# OverCurrent_Indicators.net
KiCad netlist of a schematic drawn in Altium Designer
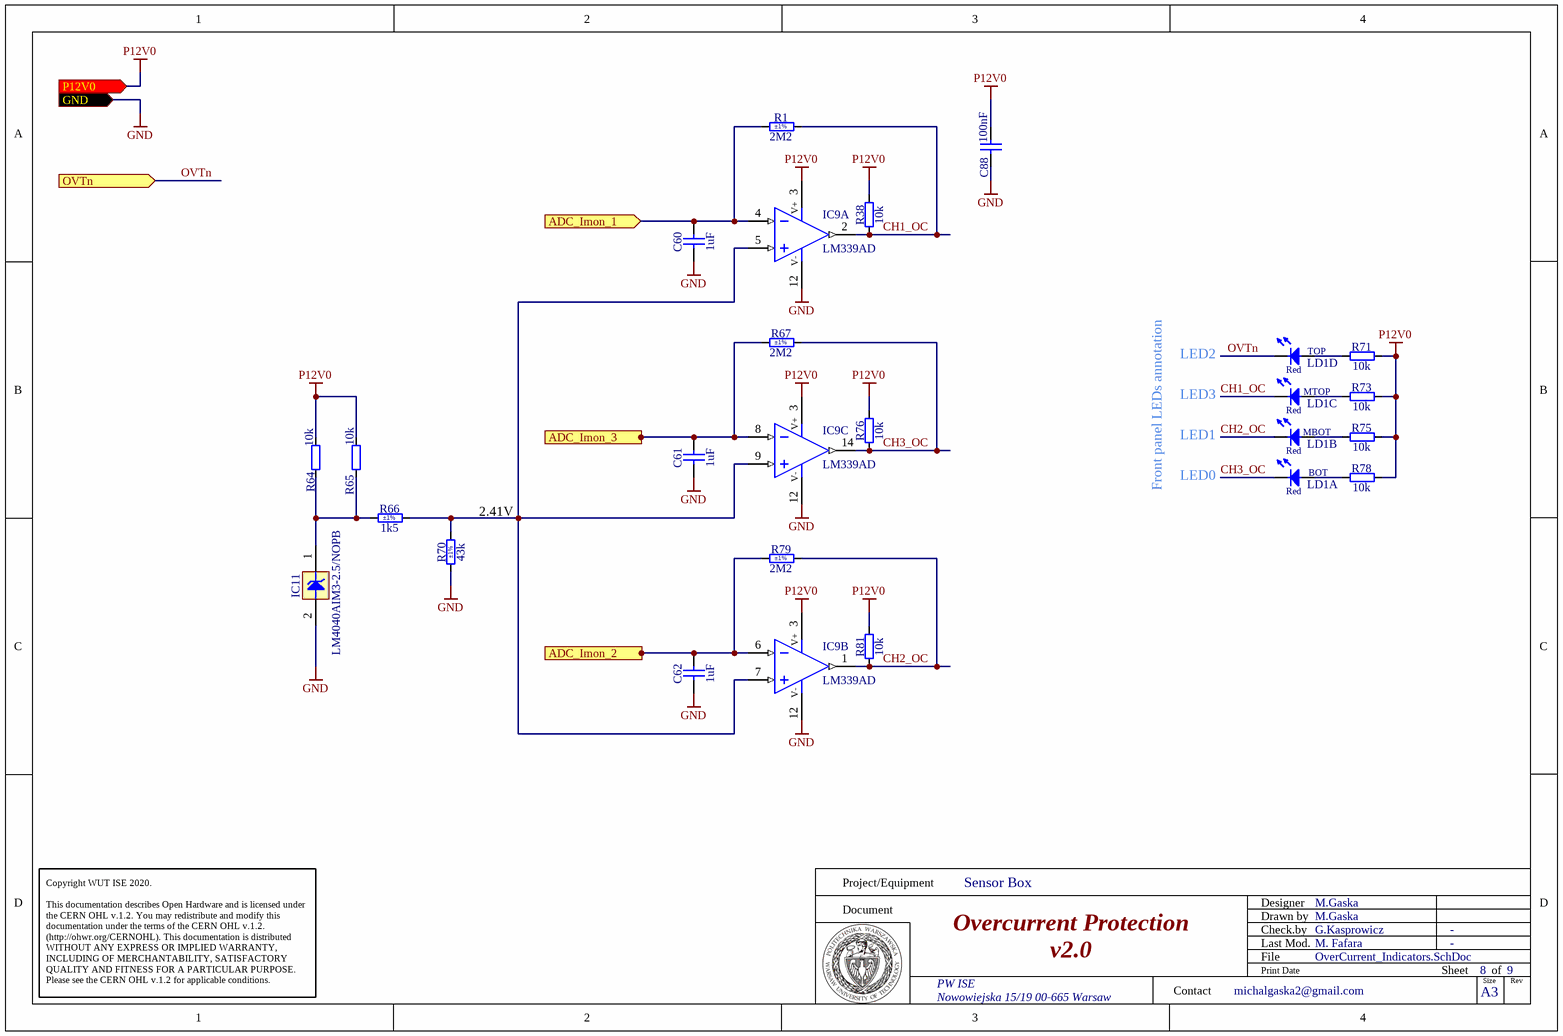
[diagram p0: OverCurrent_Indicators.SchDoc]

(export (version "E")
  (design (tool "Eeschema 10.0.6"))
  (components
    (comp (ref "C60")
      (value "1uF")
      (footprint "CAPC1608X87N")
      (description "Non-polarised capacitor")
      (fields
        (field (name "PART NUMBER") "CC0603_1UF_25V_10%_X7R")
        (field (name "VOLTAGE") "25V")
        (field (name "AUTHOR") "CERN DEM JLC")
      )
      (libsource (lib "Capacitors") (part "Capacitor - non polarized"))
    )
    (comp (ref "C61")
      (value "1uF")
      (footprint "CAPC1608X87N")
      (description "Non-polarised capacitor")
      (fields
        (field (name "PART NUMBER") "CC0603_1UF_25V_10%_X7R")
        (field (name "VOLTAGE") "25V")
        (field (name "AUTHOR") "CERN DEM JLC")
      )
      (libsource (lib "Capacitors") (part "Capacitor - non polarized"))
    )
    (comp (ref "C62")
      (value "1uF")
      (footprint "CAPC1608X87N")
      (description "Non-polarised capacitor")
      (fields
        (field (name "PART NUMBER") "CC0603_1UF_25V_10%_X7R")
        (field (name "VOLTAGE") "25V")
        (field (name "AUTHOR") "CERN DEM JLC")
      )
      (libsource (lib "Capacitors") (part "Capacitor - non polarized"))
    )
    (comp (ref "C88")
      (value "100nF")
      (footprint "CAPC1608X87N")
      (description "Non-polarised capacitor")
      (fields
        (field (name "PART NUMBER") "CC0603_100NF_50V_10%_X7R")
        (field (name "VOLTAGE") "50V")
        (field (name "AUTHOR") "CERN DEM JLC")
      )
      (libsource (lib "Capacitors") (part "Capacitor - non polarized"))
    )
    (comp (ref "IC9")
      (value "LM339AD")
      (footprint "SOIC127P600X175-14N")
      (description "Quad Operational Amplifier")
      (fields (field (name "MANUFACTURER") "TEXAS INSTRUMENTS") (field (name "AUTHOR") "CERN DEM JLC"))
      (libsource (lib "ICs And Semiconductors") (part "Operational Amplifier x4 Type2"))
    )
    (comp (ref "IC11")
      (value "LM4040AIM3-2.5/NOPB")
      (footprint "SOT95P251X112-3N")
      (description "Precision Micropower Shunt Voltage Reference")
      (fields
        (field (name "MANUFACTURER") "TEXAS INSTRUMENTS")
        (field (name "MANUFACTURER PART NUMBER") "LM4040AIM3-2.5")
        (field (name "AUTHOR") "CERN DEM JLC")
      )
      (libsource (lib "ICs And Semiconductors") (part "LM4040AIM3"))
    )
    (comp (ref "LD1")
      (value "~")
      (footprint "LED_BIVAR_H485CHDL")
      (description "LED x4 Red 1C2A-BOT_3C4A_5C6A_7C8A-TOP")
      (fields
        (field (name "PART NUMBER") "LED_BIVAR_H485CHDL")
        (field (name "MANUFACTURER") "BIVAR")
        (field (name "AUTHOR") "CERN DEM JLC")
      )
      (libsource (lib "ICs And Semiconductors") (part "LED x4 Red 1C2A-BOT_3C4A_5C6A_7C8A-TOP"))
    )
    (comp (ref "R1")
      (value "2M2")
      (footprint "RESC1608X55N")
      (description "Resistor - 1%")
      (fields
        (field (name "TOLERANCE") "±1%")
        (field (name "PART NUMBER") "R0603_2M2_1%_0.1W_100PPM")
        (field (name "POWER") "0.1W")
        (field (name "AUTHOR") "CERN DEM JLC")
      )
      (libsource (lib "Resistors") (part "Resistor - 1%"))
    )
    (comp (ref "R38")
      (value "10k")
      (footprint "RESC1608X55N")
      (description "Resistor - 1%")
      (fields
        (field (name "PART NUMBER") "R0603_10K_1%_0.1W_100PPM")
        (field (name "POWER") "0.1W")
        (field (name "AUTHOR") "CERN DEM JLC")
      )
      (libsource (lib "Resistors") (part "Resistor - 1%"))
    )
    (comp (ref "R64")
      (value "10k")
      (footprint "RESC1608X55N")
      (description "Resistor - 1%")
      (fields
        (field (name "PART NUMBER") "R0603_10K_1%_0.1W_100PPM")
        (field (name "POWER") "0.1W")
        (field (name "AUTHOR") "CERN DEM JLC")
      )
      (libsource (lib "Resistors") (part "Resistor - 1%"))
    )
    (comp (ref "R65")
      (value "10k")
      (footprint "RESC1608X55N")
      (description "Resistor - 1%")
      (fields
        (field (name "PART NUMBER") "R0603_10K_1%_0.1W_100PPM")
        (field (name "POWER") "0.1W")
        (field (name "AUTHOR") "CERN DEM JLC")
      )
      (libsource (lib "Resistors") (part "Resistor - 1%"))
    )
    (comp (ref "R66")
      (value "1k5")
      (footprint "RESC1608X55N")
      (description "Resistor - 1%")
      (fields
        (field (name "TOLERANCE") "±1%")
        (field (name "PART NUMBER") "R0603_1K5_1%_0.1W_100PPM")
        (field (name "POWER") "0.1W")
        (field (name "AUTHOR") "CERN DEM JLC")
      )
      (libsource (lib "Resistors") (part "Resistor - 1%"))
    )
    (comp (ref "R67")
      (value "2M2")
      (footprint "RESC1608X55N")
      (description "Resistor - 1%")
      (fields
        (field (name "TOLERANCE") "±1%")
        (field (name "PART NUMBER") "R0603_2M2_1%_0.1W_100PPM")
        (field (name "POWER") "0.1W")
        (field (name "AUTHOR") "CERN DEM JLC")
      )
      (libsource (lib "Resistors") (part "Resistor - 1%"))
    )
    (comp (ref "R70")
      (value "43k")
      (footprint "RESC1608X55N")
      (description "Resistor - 1%")
      (fields
        (field (name "TOLERANCE") "±1%")
        (field (name "PART NUMBER") "R0603_43K_1%_0.1W_100PPM")
        (field (name "POWER") "0.1W")
        (field (name "AUTHOR") "CERN DEM JLC")
      )
      (libsource (lib "Resistors") (part "Resistor - 1%"))
    )
    (comp (ref "R71")
      (value "10k")
      (footprint "RESC1608X55N")
      (description "Resistor - 1%")
      (fields
        (field (name "PART NUMBER") "R0603_10K_1%_0.1W_100PPM")
        (field (name "POWER") "0.1W")
        (field (name "AUTHOR") "CERN DEM JLC")
      )
      (libsource (lib "Resistors") (part "Resistor - 1%"))
    )
    (comp (ref "R73")
      (value "10k")
      (footprint "RESC1608X55N")
      (description "Resistor - 1%")
      (fields
        (field (name "PART NUMBER") "R0603_10K_1%_0.1W_100PPM")
        (field (name "POWER") "0.1W")
        (field (name "AUTHOR") "CERN DEM JLC")
      )
      (libsource (lib "Resistors") (part "Resistor - 1%"))
    )
    (comp (ref "R75")
      (value "10k")
      (footprint "RESC1608X55N")
      (description "Resistor - 1%")
      (fields
        (field (name "PART NUMBER") "R0603_10K_1%_0.1W_100PPM")
        (field (name "POWER") "0.1W")
        (field (name "AUTHOR") "CERN DEM JLC")
      )
      (libsource (lib "Resistors") (part "Resistor - 1%"))
    )
    (comp (ref "R76")
      (value "10k")
      (footprint "RESC1608X55N")
      (description "Resistor - 1%")
      (fields
        (field (name "PART NUMBER") "R0603_10K_1%_0.1W_100PPM")
        (field (name "POWER") "0.1W")
        (field (name "AUTHOR") "CERN DEM JLC")
      )
      (libsource (lib "Resistors") (part "Resistor - 1%"))
    )
    (comp (ref "R78")
      (value "10k")
      (footprint "RESC1608X55N")
      (description "Resistor - 1%")
      (fields
        (field (name "PART NUMBER") "R0603_10K_1%_0.1W_100PPM")
        (field (name "POWER") "0.1W")
        (field (name "AUTHOR") "CERN DEM JLC")
      )
      (libsource (lib "Resistors") (part "Resistor - 1%"))
    )
    (comp (ref "R79")
      (value "2M2")
      (footprint "RESC1608X55N")
      (description "Resistor - 1%")
      (fields
        (field (name "TOLERANCE") "±1%")
        (field (name "PART NUMBER") "R0603_2M2_1%_0.1W_100PPM")
        (field (name "POWER") "0.1W")
        (field (name "AUTHOR") "CERN DEM JLC")
      )
      (libsource (lib "Resistors") (part "Resistor - 1%"))
    )
    (comp (ref "R81")
      (value "10k")
      (footprint "RESC1608X55N")
      (description "Resistor - 1%")
      (fields
        (field (name "PART NUMBER") "R0603_10K_1%_0.1W_100PPM")
        (field (name "POWER") "0.1W")
        (field (name "AUTHOR") "CERN DEM JLC")
      )
      (libsource (lib "Resistors") (part "Resistor - 1%"))
    )
  )
  (nets
    (net (code "1") (name "/ADC_Imon_1") (class "Default")
      (node (ref "C60") (pin "2") (pinfunction "2_2") (pintype "passive"))
      (node (ref "IC9") (pin "4") (pinfunction "IN-_4") (pintype "input"))
      (node (ref "R1") (pin "1") (pinfunction "1_1") (pintype "passive"))
    )
    (net (code "2") (name "/ADC_Imon_2") (class "Default")
      (node (ref "C62") (pin "2") (pinfunction "2_2") (pintype "passive"))
      (node (ref "IC9") (pin "6") (pinfunction "IN-_6") (pintype "input"))
      (node (ref "R79") (pin "1") (pinfunction "1_1") (pintype "passive"))
    )
    (net (code "3") (name "/ADC_Imon_3") (class "Default")
      (node (ref "C61") (pin "2") (pinfunction "2_2") (pintype "passive"))
      (node (ref "IC9") (pin "8") (pinfunction "IN-_8") (pintype "input"))
      (node (ref "R67") (pin "1") (pinfunction "1_1") (pintype "passive"))
    )
    (net (code "4") (name "/CH1_OC") (class "Default")
      (node (ref "IC9") (pin "2") (pinfunction "OUT_2") (pintype "output"))
      (node (ref "LD1") (pin "5") (pinfunction "C_5") (pintype "passive"))
      (node (ref "R1") (pin "2") (pinfunction "2_2") (pintype "passive"))
      (node (ref "R38") (pin "1") (pinfunction "1_1") (pintype "passive"))
    )
    (net (code "5") (name "/CH2_OC") (class "Default")
      (node (ref "IC9") (pin "1") (pinfunction "OUT_1") (pintype "output"))
      (node (ref "LD1") (pin "3") (pinfunction "C_3") (pintype "passive"))
      (node (ref "R79") (pin "2") (pinfunction "2_2") (pintype "passive"))
      (node (ref "R81") (pin "1") (pinfunction "1_1") (pintype "passive"))
    )
    (net (code "6") (name "/CH3_OC") (class "Default")
      (node (ref "IC9") (pin "14") (pinfunction "OUT_14") (pintype "output"))
      (node (ref "LD1") (pin "1") (pinfunction "C_1") (pintype "passive"))
      (node (ref "R67") (pin "2") (pinfunction "2_2") (pintype "passive"))
      (node (ref "R76") (pin "1") (pinfunction "1_1") (pintype "passive"))
    )
    (net (code "7") (name "/OVTn") (class "Default")
      (node (ref "LD1") (pin "7") (pinfunction "C_7") (pintype "passive"))
    )
    (net (code "8") (name "GND") (class "Default")
      (node (ref "C60") (pin "1") (pinfunction "1_1") (pintype "passive"))
      (node (ref "C61") (pin "1") (pinfunction "1_1") (pintype "passive"))
      (node (ref "C62") (pin "1") (pinfunction "1_1") (pintype "passive"))
      (node (ref "C88") (pin "1") (pinfunction "1_1") (pintype "passive"))
      (node (ref "IC11") (pin "2") (pinfunction "A_2") (pintype "passive"))
      (node (ref "IC9") (pin "12") (pinfunction "V-_12") (pintype "power_in"))
      (node (ref "R70") (pin "1") (pinfunction "1_1") (pintype "passive"))
    )
    (net (code "9") (name "Net-(IC9A-IN+)") (class "Default")
      (node (ref "IC9") (pin "5") (pinfunction "IN+_5") (pintype "input"))
      (node (ref "IC9") (pin "7") (pinfunction "IN+_7") (pintype "input"))
      (node (ref "IC9") (pin "9") (pinfunction "IN+_9") (pintype "input"))
      (node (ref "R66") (pin "2") (pinfunction "2_2") (pintype "passive"))
      (node (ref "R70") (pin "2") (pinfunction "2_2") (pintype "passive"))
    )
    (net (code "10") (name "Net-(IC11-C)") (class "Default")
      (node (ref "IC11") (pin "1") (pinfunction "C_1") (pintype "passive"))
      (node (ref "R64") (pin "1") (pinfunction "1_1") (pintype "passive"))
      (node (ref "R65") (pin "1") (pinfunction "1_1") (pintype "passive"))
      (node (ref "R66") (pin "1") (pinfunction "1_1") (pintype "passive"))
    )
    (net (code "11") (name "Net-(LD1A-A)") (class "Default")
      (node (ref "LD1") (pin "2") (pinfunction "A_2") (pintype "passive"))
      (node (ref "R78") (pin "2") (pinfunction "2_2") (pintype "passive"))
    )
    (net (code "12") (name "Net-(LD1B-A)") (class "Default")
      (node (ref "LD1") (pin "4") (pinfunction "A_4") (pintype "passive"))
      (node (ref "R75") (pin "2") (pinfunction "2_2") (pintype "passive"))
    )
    (net (code "13") (name "Net-(LD1C-A)") (class "Default")
      (node (ref "LD1") (pin "6") (pinfunction "A_6") (pintype "passive"))
      (node (ref "R73") (pin "2") (pinfunction "2_2") (pintype "passive"))
    )
    (net (code "14") (name "Net-(LD1D-A)") (class "Default")
      (node (ref "LD1") (pin "8") (pinfunction "A_8") (pintype "passive"))
      (node (ref "R71") (pin "2") (pinfunction "2_2") (pintype "passive"))
    )
    (net (code "15") (name "P12V0") (class "Default")
      (node (ref "C88") (pin "2") (pinfunction "2_2") (pintype "passive"))
      (node (ref "IC9") (pin "3") (pinfunction "V+_3") (pintype "power_in"))
      (node (ref "R38") (pin "2") (pinfunction "2_2") (pintype "passive"))
      (node (ref "R64") (pin "2") (pinfunction "2_2") (pintype "passive"))
      (node (ref "R65") (pin "2") (pinfunction "2_2") (pintype "passive"))
      (node (ref "R71") (pin "1") (pinfunction "1_1") (pintype "passive"))
      (node (ref "R73") (pin "1") (pinfunction "1_1") (pintype "passive"))
      (node (ref "R75") (pin "1") (pinfunction "1_1") (pintype "passive"))
      (node (ref "R76") (pin "2") (pinfunction "2_2") (pintype "passive"))
      (node (ref "R78") (pin "1") (pinfunction "1_1") (pintype "passive"))
      (node (ref "R81") (pin "2") (pinfunction "2_2") (pintype "passive"))
    )
  )
)
